# DualModeCar_Sch.net
KiCad netlist of a schematic drawn in Altium Designer
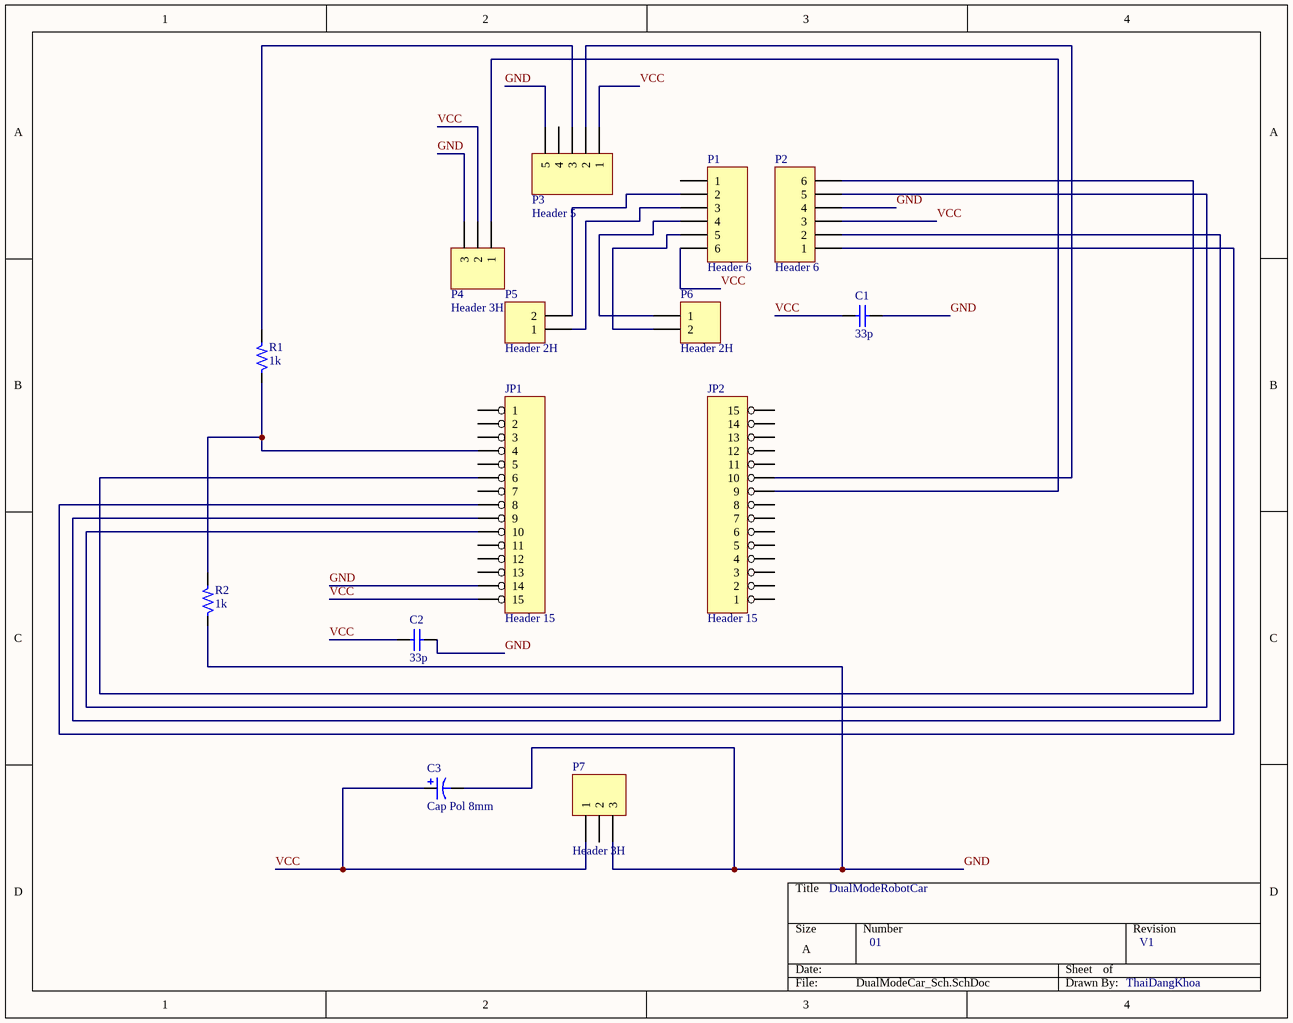
[diagram p0: DualModeCar_Sch.SchDoc]

(export (version "E")
  (design (tool "Eeschema 10.0.6"))
  (components
    (comp (ref "C1")
      (value "33p")
      (footprint "Tu-pico")
      (description "Capacitor")
      (fields (field (name "Comment") "Capacitor Ceramic") (field (name "PUBLISHER") "Altium Limited"))
      (libsource (lib "Cty1") (part "CapCeramic"))
    )
    (comp (ref "C2")
      (value "33p")
      (footprint "Tu-pico")
      (description "Capacitor")
      (fields (field (name "Comment") "Capacitor Ceramic") (field (name "PUBLISHER") "Altium Limited"))
      (libsource (lib "Cty1") (part "CapCeramic"))
    )
    (comp (ref "C3")
      (value "Cap Pol 8mm")
      (footprint "C10mm")
      (description "Polarized Capacitor (Axial)")
      (fields (field (name "PUBLISHER") "Altium Limited"))
      (libsource (lib "Cty1") (part "Cap Pol 8mm"))
    )
    (comp (ref "JP1")
      (value "Header 15")
      (footprint "HDR1X15")
      (description "Header, 15-Pin, Right Angle")
      (libsource (lib "Cty1") (part "Header 15"))
    )
    (comp (ref "JP2")
      (value "Header 15")
      (footprint "HDR1X15")
      (description "Header, 15-Pin, Right Angle")
      (libsource (lib "") (part "Header 15_1"))
    )
    (comp (ref "P1")
      (value "Header 6")
      (footprint "HDR1X6")
      (description "Header, 6-Pin")
      (fields (field (name "PUBLISHER") "Altium Limited"))
      (libsource (lib "Cty1") (part "Header 6"))
    )
    (comp (ref "P2")
      (value "Header 6")
      (footprint "HDR1X6")
      (description "Header, 6-Pin")
      (fields (field (name "PUBLISHER") "Altium Limited"))
      (libsource (lib "") (part "Header 6_1"))
    )
    (comp (ref "P3")
      (value "Header 5")
      (footprint "HDR1X5")
      (description "Header, 5-Pin")
      (fields (field (name "PUBLISHER") "Altium Limited"))
      (libsource (lib "Cty1") (part "Header 5"))
    )
    (comp (ref "P4")
      (value "Header 3H")
      (footprint "HDR1X3H")
      (description "Header, 3-Pin, Right Angle")
      (fields (field (name "PUBLISHER") "Altium Limited"))
      (libsource (lib "Cty1") (part "Header 3H"))
    )
    (comp (ref "P5")
      (value "Header 2H")
      (footprint "HDR1X2H")
      (description "Header, 2-Pin, Right Angle")
      (fields (field (name "PUBLISHER") "Altium Limited"))
      (libsource (lib "Cty1") (part "Header 2H"))
    )
    (comp (ref "P6")
      (value "Header 2H")
      (footprint "HDR1X2H")
      (description "Header, 2-Pin, Right Angle")
      (fields (field (name "PUBLISHER") "Altium Limited"))
      (libsource (lib "") (part "Header 2H_1"))
    )
    (comp (ref "P7")
      (value "Header 3H")
      (footprint "HDR1X3H")
      (description "Header, 3-Pin, Right Angle")
      (fields (field (name "PUBLISHER") "Altium Limited"))
      (libsource (lib "") (part "Header 3H_1"))
    )
    (comp (ref "R1")
      (value "1k")
      (footprint "RES 1/4W CFR25")
      (description "Resistor 1/4W")
      (libsource (lib "Devzone_SCHLib") (part "Res"))
    )
    (comp (ref "R2")
      (value "1k")
      (footprint "RES 1/4W CFR25")
      (description "Resistor 1/4W")
      (libsource (lib "Devzone_SCHLib") (part "Res"))
    )
  )
  (nets
    (net (code "1") (name "/GND") (class "Default")
      (node (ref "C1") (pin "2") (pinfunction "2_2") (pintype "passive"))
      (node (ref "C2") (pin "2") (pinfunction "2_2") (pintype "passive"))
      (node (ref "C3") (pin "2") (pinfunction "2_2") (pintype "passive"))
      (node (ref "JP1") (pin "14") (pinfunction "14_14") (pintype "passive"))
      (node (ref "P2") (pin "4") (pinfunction "4_4") (pintype "passive"))
      (node (ref "P3") (pin "5") (pinfunction "5_5") (pintype "passive"))
      (node (ref "P4") (pin "3") (pinfunction "3_3") (pintype "passive"))
      (node (ref "P7") (pin "3") (pinfunction "3_3") (pintype "passive"))
      (node (ref "R2") (pin "1") (pinfunction "1_1") (pintype "passive"))
    )
    (net (code "2") (name "/VCC") (class "Default")
      (node (ref "C1") (pin "1") (pinfunction "1_1") (pintype "passive"))
      (node (ref "C2") (pin "1") (pinfunction "1_1") (pintype "passive"))
      (node (ref "C3") (pin "1") (pinfunction "1_1") (pintype "passive"))
      (node (ref "JP1") (pin "15") (pinfunction "15_15") (pintype "passive"))
      (node (ref "P1") (pin "6") (pinfunction "6_6") (pintype "passive"))
      (node (ref "P2") (pin "3") (pinfunction "3_3") (pintype "passive"))
      (node (ref "P3") (pin "1") (pinfunction "1_1") (pintype "passive"))
      (node (ref "P4") (pin "2") (pinfunction "2_2") (pintype "passive"))
      (node (ref "P7") (pin "1") (pinfunction "1_1") (pintype "passive"))
    )
    (net (code "3") (name "Net-(JP1-Pad4)") (class "Default")
      (node (ref "JP1") (pin "4") (pinfunction "4_4") (pintype "passive"))
      (node (ref "R1") (pin "1") (pinfunction "1_1") (pintype "passive"))
      (node (ref "R2") (pin "2") (pinfunction "2_2") (pintype "passive"))
    )
    (net (code "4") (name "Net-(JP1-Pad6)") (class "Default")
      (node (ref "JP1") (pin "6") (pinfunction "6_6") (pintype "passive"))
      (node (ref "P2") (pin "6") (pinfunction "6_6") (pintype "passive"))
    )
    (net (code "5") (name "Net-(JP1-Pad8)") (class "Default")
      (node (ref "JP1") (pin "8") (pinfunction "8_8") (pintype "passive"))
      (node (ref "P2") (pin "1") (pinfunction "1_1") (pintype "passive"))
    )
    (net (code "6") (name "Net-(JP1-Pad9)") (class "Default")
      (node (ref "JP1") (pin "9") (pinfunction "9_9") (pintype "passive"))
      (node (ref "P2") (pin "2") (pinfunction "2_2") (pintype "passive"))
    )
    (net (code "7") (name "Net-(JP1-Pad10)") (class "Default")
      (node (ref "JP1") (pin "10") (pinfunction "10_10") (pintype "passive"))
      (node (ref "P2") (pin "5") (pinfunction "5_5") (pintype "passive"))
    )
    (net (code "8") (name "Net-(JP2-Pad9)") (class "Default")
      (node (ref "JP2") (pin "9") (pinfunction "9_9") (pintype "passive"))
      (node (ref "P4") (pin "1") (pinfunction "1_1") (pintype "passive"))
    )
    (net (code "9") (name "Net-(JP2-Pad10)") (class "Default")
      (node (ref "JP2") (pin "10") (pinfunction "10_10") (pintype "passive"))
      (node (ref "P3") (pin "2") (pinfunction "2_2") (pintype "passive"))
    )
    (net (code "10") (name "Net-(P1-Pad2)") (class "Default")
      (node (ref "P1") (pin "2") (pinfunction "2_2") (pintype "passive"))
      (node (ref "P5") (pin "2") (pinfunction "2_2") (pintype "passive"))
    )
    (net (code "11") (name "Net-(P1-Pad3)") (class "Default")
      (node (ref "P1") (pin "3") (pinfunction "3_3") (pintype "passive"))
      (node (ref "P5") (pin "1") (pinfunction "1_1") (pintype "passive"))
    )
    (net (code "12") (name "Net-(P1-Pad4)") (class "Default")
      (node (ref "P1") (pin "4") (pinfunction "4_4") (pintype "passive"))
      (node (ref "P6") (pin "1") (pinfunction "1_1") (pintype "passive"))
    )
    (net (code "13") (name "Net-(P1-Pad5)") (class "Default")
      (node (ref "P1") (pin "5") (pinfunction "5_5") (pintype "passive"))
      (node (ref "P6") (pin "2") (pinfunction "2_2") (pintype "passive"))
    )
    (net (code "14") (name "Net-(P3-Pad3)") (class "Default")
      (node (ref "P3") (pin "3") (pinfunction "3_3") (pintype "passive"))
      (node (ref "R1") (pin "2") (pinfunction "2_2") (pintype "passive"))
    )
    (net (code "15") (name "unconnected-(JP1-Pad1)") (class "Default")
      (node (ref "JP1") (pin "1") (pinfunction "1_1") (pintype "passive"))
    )
    (net (code "16") (name "unconnected-(JP1-Pad2)") (class "Default")
      (node (ref "JP1") (pin "2") (pinfunction "2_2") (pintype "passive"))
    )
    (net (code "17") (name "unconnected-(JP1-Pad3)") (class "Default")
      (node (ref "JP1") (pin "3") (pinfunction "3_3") (pintype "passive"))
    )
    (net (code "18") (name "unconnected-(JP1-Pad5)") (class "Default")
      (node (ref "JP1") (pin "5") (pinfunction "5_5") (pintype "passive"))
    )
    (net (code "19") (name "unconnected-(JP1-Pad7)") (class "Default")
      (node (ref "JP1") (pin "7") (pinfunction "7_7") (pintype "passive"))
    )
    (net (code "20") (name "unconnected-(JP1-Pad11)") (class "Default")
      (node (ref "JP1") (pin "11") (pinfunction "11_11") (pintype "passive"))
    )
    (net (code "21") (name "unconnected-(JP1-Pad12)") (class "Default")
      (node (ref "JP1") (pin "12") (pinfunction "12_12") (pintype "passive"))
    )
    (net (code "22") (name "unconnected-(JP1-Pad13)") (class "Default")
      (node (ref "JP1") (pin "13") (pinfunction "13_13") (pintype "passive"))
    )
    (net (code "23") (name "unconnected-(JP2-Pad1)") (class "Default")
      (node (ref "JP2") (pin "1") (pinfunction "1_1") (pintype "passive"))
    )
    (net (code "24") (name "unconnected-(JP2-Pad2)") (class "Default")
      (node (ref "JP2") (pin "2") (pinfunction "2_2") (pintype "passive"))
    )
    (net (code "25") (name "unconnected-(JP2-Pad3)") (class "Default")
      (node (ref "JP2") (pin "3") (pinfunction "3_3") (pintype "passive"))
    )
    (net (code "26") (name "unconnected-(JP2-Pad4)") (class "Default")
      (node (ref "JP2") (pin "4") (pinfunction "4_4") (pintype "passive"))
    )
    (net (code "27") (name "unconnected-(JP2-Pad5)") (class "Default")
      (node (ref "JP2") (pin "5") (pinfunction "5_5") (pintype "passive"))
    )
    (net (code "28") (name "unconnected-(JP2-Pad6)") (class "Default")
      (node (ref "JP2") (pin "6") (pinfunction "6_6") (pintype "passive"))
    )
    (net (code "29") (name "unconnected-(JP2-Pad7)") (class "Default")
      (node (ref "JP2") (pin "7") (pinfunction "7_7") (pintype "passive"))
    )
    (net (code "30") (name "unconnected-(JP2-Pad8)") (class "Default")
      (node (ref "JP2") (pin "8") (pinfunction "8_8") (pintype "passive"))
    )
    (net (code "31") (name "unconnected-(JP2-Pad11)") (class "Default")
      (node (ref "JP2") (pin "11") (pinfunction "11_11") (pintype "passive"))
    )
    (net (code "32") (name "unconnected-(JP2-Pad12)") (class "Default")
      (node (ref "JP2") (pin "12") (pinfunction "12_12") (pintype "passive"))
    )
    (net (code "33") (name "unconnected-(JP2-Pad13)") (class "Default")
      (node (ref "JP2") (pin "13") (pinfunction "13_13") (pintype "passive"))
    )
    (net (code "34") (name "unconnected-(JP2-Pad14)") (class "Default")
      (node (ref "JP2") (pin "14") (pinfunction "14_14") (pintype "passive"))
    )
    (net (code "35") (name "unconnected-(JP2-Pad15)") (class "Default")
      (node (ref "JP2") (pin "15") (pinfunction "15_15") (pintype "passive"))
    )
    (net (code "36") (name "unconnected-(P1-Pad1)") (class "Default")
      (node (ref "P1") (pin "1") (pinfunction "1_1") (pintype "passive"))
    )
    (net (code "37") (name "unconnected-(P3-Pad4)") (class "Default")
      (node (ref "P3") (pin "4") (pinfunction "4_4") (pintype "passive"))
    )
    (net (code "38") (name "unconnected-(P7-Pad2)") (class "Default")
      (node (ref "P7") (pin "2") (pinfunction "2_2") (pintype "passive"))
    )
  )
)
